# 03_-_MCU_and_Conn.net
KiCad netlist of a schematic drawn in Altium Designer
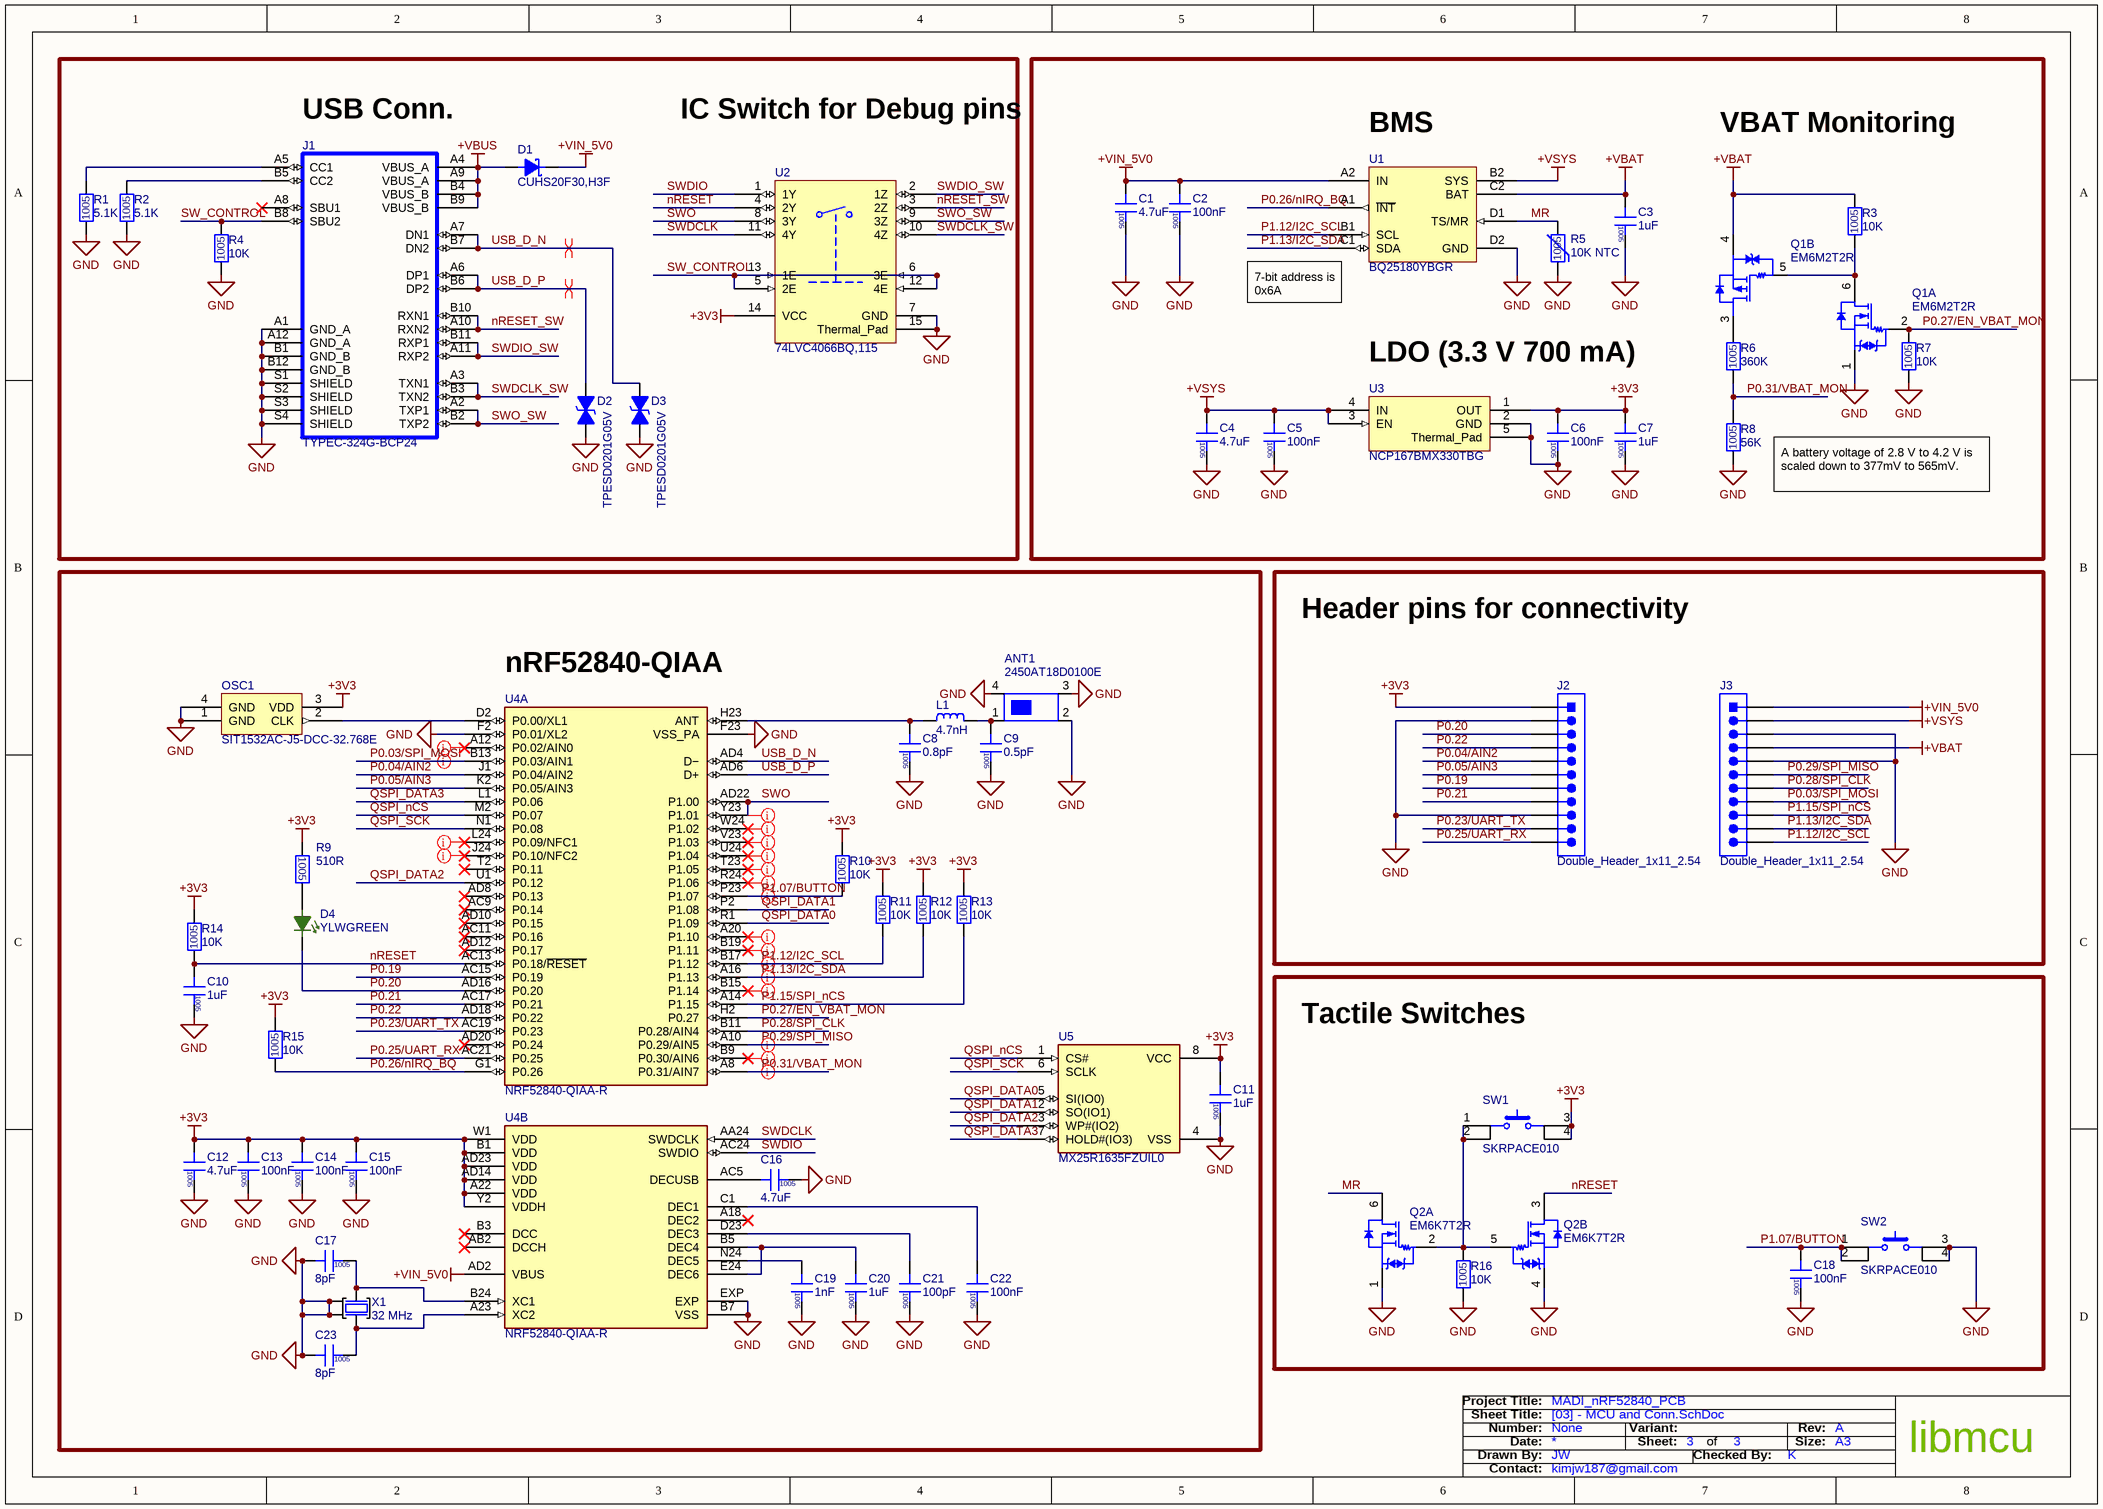
[diagram p0: [03] - MCU and Conn.SchDoc]

(export (version "E")
  (design (tool "Eeschema 10.0.6"))
  (components
    (comp (ref "ANT1")
      (value "2450AT18D0100E")
      (footprint "2450AT18D0100E")
      (description "RF ANT 2.4GHZ CHIP SOLDER SMD")
      (fields (field (name "MANUFACTURER") "Johanson"))
      (libsource (lib "Schlib-master") (part "2450AT18D0100E"))
    )
    (comp (ref "C1")
      (value "4.7uF")
      (footprint "CAPC1005X06N")
      (description "CAP CER 4.7UF 10V X5R 0402")
      (fields
        (field (name "MANUFACTURER") "Samsung")
        (field (name "MANUFACTURER PART NUMBER") "CL05A475MP5NRNC")
      )
      (libsource (lib "Schlib-master") (part "CL05A475MP5NRNC"))
    )
    (comp (ref "C2")
      (value "100nF")
      (footprint "CAPC1005X06N")
      (description "CAP CER 0.1UF 16V X7R 0402")
      (fields
        (field (name "MANUFACTURER") "Samsung")
        (field (name "MANUFACTURER PART NUMBER") "CL05B104KO5NNNC")
      )
      (libsource (lib "Schlib-master") (part "CL05B104KO5NNNC"))
    )
    (comp (ref "C3")
      (value "1uF")
      (footprint "CAPC1005X06N")
      (description "CAP CER 1UF 16V X5R 0402")
      (fields
        (field (name "MANUFACTURER") "Samsung")
        (field (name "MANUFACTURER PART NUMBER") "CL05A105KO5NNNC")
      )
      (libsource (lib "Schlib-master") (part "CL05A105KO5NNNC"))
    )
    (comp (ref "C4")
      (value "4.7uF")
      (footprint "CAPC1005X06N")
      (description "CAP CER 4.7UF 10V X5R 0402")
      (fields
        (field (name "MANUFACTURER") "Samsung")
        (field (name "MANUFACTURER PART NUMBER") "CL05A475MP5NRNC")
      )
      (libsource (lib "Schlib-master") (part "CL05A475MP5NRNC"))
    )
    (comp (ref "C5")
      (value "100nF")
      (footprint "CAPC1005X06N")
      (description "CAP CER 0.1UF 16V X7R 0402")
      (fields
        (field (name "MANUFACTURER") "Samsung")
        (field (name "MANUFACTURER PART NUMBER") "CL05B104KO5NNNC")
      )
      (libsource (lib "Schlib-master") (part "CL05B104KO5NNNC"))
    )
    (comp (ref "C6")
      (value "100nF")
      (footprint "CAPC1005X06N")
      (description "CAP CER 0.1UF 16V X7R 0402")
      (fields
        (field (name "MANUFACTURER") "Samsung")
        (field (name "MANUFACTURER PART NUMBER") "CL05B104KO5NNNC")
      )
      (libsource (lib "Schlib-master") (part "CL05B104KO5NNNC"))
    )
    (comp (ref "C7")
      (value "1uF")
      (footprint "CAPC1005X06N")
      (description "CAP CER 1UF 16V X5R 0402")
      (fields
        (field (name "MANUFACTURER") "Samsung")
        (field (name "MANUFACTURER PART NUMBER") "CL05A105KO5NNNC")
      )
      (libsource (lib "Schlib-master") (part "CL05A105KO5NNNC"))
    )
    (comp (ref "C8")
      (value "0.8pF")
      (footprint "CAPC1005X06N")
      (description "CAP CER 0.8PF 50V C0G/NP0 0402")
      (fields
        (field (name "MANUFACTURER") "Murata")
        (field (name "MANUFACTURER PART NUMBER") "GJM1555C1HR80BB01D")
      )
      (libsource (lib "Schlib-master") (part "GJM1555C1HR80BB01D"))
    )
    (comp (ref "C9")
      (value "0.5pF")
      (footprint "CAPC1005X06N")
      (description "CAP CER 0.5PF 50V C0G/NP0 0402")
      (fields
        (field (name "MANUFACTURER") "Murata")
        (field (name "MANUFACTURER PART NUMBER") "GJM1555C1HR50BB01D")
      )
      (libsource (lib "Schlib-master") (part "GJM1555C1HR50BB01D"))
    )
    (comp (ref "C10")
      (value "1uF")
      (footprint "CAPC1005X06N")
      (description "CAP CER 1UF 16V X5R 0402")
      (fields
        (field (name "MANUFACTURER") "Samsung")
        (field (name "MANUFACTURER PART NUMBER") "CL05A105KO5NNNC")
      )
      (libsource (lib "Schlib-master") (part "CL05A105KO5NNNC"))
    )
    (comp (ref "C11")
      (value "1uF")
      (footprint "CAPC1005X06N")
      (description "CAP CER 1UF 16V X5R 0402")
      (fields
        (field (name "MANUFACTURER") "Samsung")
        (field (name "MANUFACTURER PART NUMBER") "CL05A105KO5NNNC")
      )
      (libsource (lib "Schlib-master") (part "CL05A105KO5NNNC"))
    )
    (comp (ref "C12")
      (value "4.7uF")
      (footprint "CAPC1005X06N")
      (description "CAP CER 4.7UF 10V X5R 0402")
      (fields
        (field (name "MANUFACTURER") "Samsung")
        (field (name "MANUFACTURER PART NUMBER") "CL05A475MP5NRNC")
      )
      (libsource (lib "Schlib-master") (part "CL05A475MP5NRNC"))
    )
    (comp (ref "C13")
      (value "100nF")
      (footprint "CAPC1005X06N")
      (description "CAP CER 0.1UF 16V X7R 0402")
      (fields
        (field (name "MANUFACTURER") "Samsung")
        (field (name "MANUFACTURER PART NUMBER") "CL05B104KO5NNNC")
      )
      (libsource (lib "Schlib-master") (part "CL05B104KO5NNNC"))
    )
    (comp (ref "C14")
      (value "100nF")
      (footprint "CAPC1005X06N")
      (description "CAP CER 0.1UF 16V X7R 0402")
      (fields
        (field (name "MANUFACTURER") "Samsung")
        (field (name "MANUFACTURER PART NUMBER") "CL05B104KO5NNNC")
      )
      (libsource (lib "Schlib-master") (part "CL05B104KO5NNNC"))
    )
    (comp (ref "C15")
      (value "100nF")
      (footprint "CAPC1005X06N")
      (description "CAP CER 0.1UF 16V X7R 0402")
      (fields
        (field (name "MANUFACTURER") "Samsung")
        (field (name "MANUFACTURER PART NUMBER") "CL05B104KO5NNNC")
      )
      (libsource (lib "Schlib-master") (part "CL05B104KO5NNNC"))
    )
    (comp (ref "C16")
      (value "4.7uF")
      (footprint "CAPC1005X06N")
      (description "CAP CER 4.7UF 10V X5R 0402")
      (fields
        (field (name "MANUFACTURER") "Samsung")
        (field (name "MANUFACTURER PART NUMBER") "CL05A475MP5NRNC")
      )
      (libsource (lib "Schlib-master") (part "CL05A475MP5NRNC"))
    )
    (comp (ref "C17")
      (value "8pF")
      (footprint "CAPC1005X06N")
      (description "CAP CER 8PF 50V C0G/NP0 0402")
      (fields
        (field (name "MANUFACTURER") "Yageo")
        (field (name "MANUFACTURER PART NUMBER") "CC0402CRNPO9BN8R0")
      )
      (libsource (lib "Schlib-master") (part "CC0402CRNPO9BN8R0"))
    )
    (comp (ref "C18")
      (value "100nF")
      (footprint "CAPC1005X06N")
      (description "CAP CER 0.1UF 16V X7R 0402")
      (fields
        (field (name "MANUFACTURER") "Samsung")
        (field (name "MANUFACTURER PART NUMBER") "CL05B104KO5NNNC")
      )
      (libsource (lib "Schlib-master") (part "CL05B104KO5NNNC"))
    )
    (comp (ref "C19")
      (value "1nF")
      (footprint "CAPC1005X06N")
      (description "CAP CER 1000PF 50V X7R 0402")
      (fields
        (field (name "MANUFACTURER") "Samsung")
        (field (name "MANUFACTURER PART NUMBER") "CL05B102KB5NNNC")
      )
      (libsource (lib "Schlib-master") (part "CL05B102KB5NNNC"))
    )
    (comp (ref "C20")
      (value "1uF")
      (footprint "CAPC1005X06N")
      (description "CAP CER 1UF 16V X5R 0402")
      (fields
        (field (name "MANUFACTURER") "Samsung")
        (field (name "MANUFACTURER PART NUMBER") "CL05A105KO5NNNC")
      )
      (libsource (lib "Schlib-master") (part "CL05A105KO5NNNC"))
    )
    (comp (ref "C21")
      (value "100pF")
      (footprint "CAPC1005X06N")
      (description "CAP CER 100PF 50V C0G/NP0 0402")
      (fields
        (field (name "MANUFACTURER") "Samsung")
        (field (name "MANUFACTURER PART NUMBER") "CL05C101JB5NNNC")
      )
      (libsource (lib "Schlib-master") (part "CL05C101JB5NNNC"))
    )
    (comp (ref "C22")
      (value "100nF")
      (footprint "CAPC1005X06N")
      (description "CAP CER 0.1UF 16V X7R 0402")
      (fields
        (field (name "MANUFACTURER") "Samsung")
        (field (name "MANUFACTURER PART NUMBER") "CL05B104KO5NNNC")
      )
      (libsource (lib "Schlib-master") (part "CL05B104KO5NNNC"))
    )
    (comp (ref "C23")
      (value "8pF")
      (footprint "CAPC1005X06N")
      (description "CAP CER 8PF 50V C0G/NP0 0402")
      (fields
        (field (name "MANUFACTURER") "Yageo")
        (field (name "MANUFACTURER PART NUMBER") "CC0402CRNPO9BN8R0")
      )
      (libsource (lib "Schlib-master") (part "CC0402CRNPO9BN8R0"))
    )
    (comp (ref "D1")
      (value "CUHS20F30,H3F")
      (footprint "US2H-DIODE")
      (description "DIODE SCHOTTKY 30V 2A US2H")
      (fields (field (name "MANUFACTURER") "Toshiba"))
      (libsource (lib "Schlib-master") (part "CUHS20F30,H3F"))
    )
    (comp (ref "D2")
      (value "TPESD0201G05V")
      (footprint "DIOC0603X03N")
      (description "TVS DIODE 5.5VWM 40VC 0201")
      (fields (field (name "MANUFACTURER") "TECH PUBLIC"))
      (libsource (lib "Schlib-master") (part "TPESD0201G05V"))
    )
    (comp (ref "D3")
      (value "TPESD0201G05V")
      (footprint "DIOC0603X03N")
      (description "TVS DIODE 5.5VWM 40VC 0201")
      (fields (field (name "MANUFACTURER") "TECH PUBLIC"))
      (libsource (lib "Schlib-master") (part "TPESD0201G05V"))
    )
    (comp (ref "D4")
      (value "YLWGREEN")
      (footprint "LDIOC1608X08N")
      (description "LED YLW/GREEN DIFFUSED 1608 SMD")
      (fields
        (field (name "MANUFACTURER") "Everlight")
        (field (name "MANUFACTURER PART NUMBER") "19-217/G7C-AN1P2/3T")
      )
      (libsource (lib "Schlib-master") (part "19-217/G7C-AN1P2/3T"))
    )
    (comp (ref "J1")
      (value "TYPEC-324G-BCP24")
      (footprint "KUSBX-SMT3-CS-BTR_KYC")
      (description "CONN RCPT USB TYPE C, SMT PINS, TH SHIELD")
      (fields (field (name "MANUFACTURER") "XUNPU"))
      (libsource (lib "Schlib-master") (part "TYPEC-324G-BCP24"))
    )
    (comp (ref "J2")
      (value "Double_Header_1x11_2.54")
      (footprint "1x11_DOUBLE_HEADER_2.54")
      (libsource (lib "") (part "Double_Header_1x11_2.54_1"))
    )
    (comp (ref "J3")
      (value "Double_Header_1x11_2.54")
      (footprint "1x11_DOUBLE_HEADER_2.54")
      (libsource (lib "Schlib-master") (part "Double_Header_1x11_2.54"))
    )
    (comp (ref "L1")
      (value "4.7nH")
      (footprint "INDC1005X05N")
      (description "FIXED IND 4.7NH 400MA 180 MOHM")
      (fields
        (field (name "MANUFACTURER") "Chilisin Elec")
        (field (name "MANUFACTURER PART NUMBER") "CLH1005T-4N7S-S-NP")
      )
      (libsource (lib "Schlib-master") (part "CLH1005T-4N7S-S-NP"))
    )
    (comp (ref "OSC1")
      (value "SIT1532AC-J5-DCC-32.768E")
      (footprint "SIT1532")
      (description "MEMS OSC XO 32.7680KHZ LVCMOS")
      (fields (field (name "MANUFACTURER") "SiTime"))
      (libsource (lib "Schlib-master") (part "SIT1532AC-J5-DCC-32.768E"))
    )
    (comp (ref "Q1")
      (value "EM6M2T2R")
      (footprint "SOTFL50P160X55-6N")
      (description "MOSFET N/P-CH 20V 0.2A EMT6")
      (fields (field (name "MANUFACTURER") "Rohm"))
      (libsource (lib "Schlib-master") (part "EM6M2T2R"))
    )
    (comp (ref "Q2")
      (value "EM6K7T2R")
      (footprint "SOTFL50P160X55-6N")
      (description "MOSFET 2N-CH 20V 0.2A EMT6")
      (fields (field (name "MANUFACTURER") "Rohm"))
      (libsource (lib "Schlib-master") (part "EM6K7T2R"))
    )
    (comp (ref "R1")
      (value "5.1K")
      (footprint "RESC1005X04N")
      (description "RES SMD 5.1K OHM 1% 1/16W 0402")
      (fields
        (field (name "MANUFACTURER") "Yageo")
        (field (name "MANUFACTURER PART NUMBER") "RC0402FR-075K1L")
      )
      (libsource (lib "Schlib-master") (part "RC0402FR-075K1L"))
    )
    (comp (ref "R2")
      (value "5.1K")
      (footprint "RESC1005X04N")
      (description "RES SMD 5.1K OHM 1% 1/16W 0402")
      (fields
        (field (name "MANUFACTURER") "Yageo")
        (field (name "MANUFACTURER PART NUMBER") "RC0402FR-075K1L")
      )
      (libsource (lib "Schlib-master") (part "RC0402FR-075K1L"))
    )
    (comp (ref "R3")
      (value "10K")
      (footprint "RESC1005X04N")
      (description "RES SMD 10K OHM 1% 1/16W 0402")
      (fields
        (field (name "MANUFACTURER") "Yageo")
        (field (name "MANUFACTURER PART NUMBER") "RC0402FR-0710KL")
      )
      (libsource (lib "Schlib-master") (part "RC0402FR-0710KL"))
    )
    (comp (ref "R4")
      (value "10K")
      (footprint "RESC1005X04N")
      (description "RES SMD 10K OHM 1% 1/16W 0402")
      (fields
        (field (name "MANUFACTURER") "Yageo")
        (field (name "MANUFACTURER PART NUMBER") "RC0402FR-0710KL")
      )
      (libsource (lib "Schlib-master") (part "RC0402FR-0710KL"))
    )
    (comp (ref "R5")
      (value "10K NTC")
      (footprint "NTC1005X05N")
      (description "THERMISTOR NTC 10KOHM 3380K 0402")
      (fields
        (field (name "MANUFACTURER") "Murata")
        (field (name "MANUFACTURER PART NUMBER") "NCP15XH103F03RC")
      )
      (libsource (lib "Schlib-master") (part "NCP15XH103F03RC"))
    )
    (comp (ref "R6")
      (value "360K")
      (footprint "RESC1005X04N")
      (description "RES SMD 360K OHM 1% 1/16W 0402")
      (fields
        (field (name "MANUFACTURER") "Yageo")
        (field (name "MANUFACTURER PART NUMBER") "RC0402FR-07360KL")
      )
      (libsource (lib "Schlib-master") (part "RC0402FR-07360KL"))
    )
    (comp (ref "R7")
      (value "10K")
      (footprint "RESC1005X04N")
      (description "RES SMD 10K OHM 1% 1/16W 0402")
      (fields
        (field (name "MANUFACTURER") "Yageo")
        (field (name "MANUFACTURER PART NUMBER") "RC0402FR-0710KL")
      )
      (libsource (lib "Schlib-master") (part "RC0402FR-0710KL"))
    )
    (comp (ref "R8")
      (value "56K")
      (footprint "RESC1005X04N")
      (description "RES SMD 56K OHM 1% 1/16W 0402")
      (fields
        (field (name "MANUFACTURER") "Yageo")
        (field (name "MANUFACTURER PART NUMBER") "RC0402FR-0756KL")
      )
      (libsource (lib "Schlib-master") (part "RC0402FR-0756KL"))
    )
    (comp (ref "R9")
      (value "510R")
      (footprint "RESC1005X04N")
      (description "RES SMD 510 OHM 1% 1/16W 0402")
      (fields (field (name "TOLERANCE") "1%") (field (name "MANUFACTURER") "Yageo"))
      (libsource (lib "Schlib-master") (part "RC0402FR-07510RL"))
    )
    (comp (ref "R10")
      (value "10K")
      (footprint "RESC1005X04N")
      (description "RES SMD 10K OHM 1% 1/16W 0402")
      (fields
        (field (name "MANUFACTURER") "Yageo")
        (field (name "MANUFACTURER PART NUMBER") "RC0402FR-0710KL")
      )
      (libsource (lib "Schlib-master") (part "RC0402FR-0710KL"))
    )
    (comp (ref "R11")
      (value "10K")
      (footprint "RESC1005X04N")
      (description "RES SMD 10K OHM 1% 1/16W 0402")
      (fields
        (field (name "MANUFACTURER") "Yageo")
        (field (name "MANUFACTURER PART NUMBER") "RC0402FR-0710KL")
      )
      (libsource (lib "Schlib-master") (part "RC0402FR-0710KL"))
    )
    (comp (ref "R12")
      (value "10K")
      (footprint "RESC1005X04N")
      (description "RES SMD 10K OHM 1% 1/16W 0402")
      (fields
        (field (name "MANUFACTURER") "Yageo")
        (field (name "MANUFACTURER PART NUMBER") "RC0402FR-0710KL")
      )
      (libsource (lib "Schlib-master") (part "RC0402FR-0710KL"))
    )
    (comp (ref "R13")
      (value "10K")
      (footprint "RESC1005X04N")
      (description "RES SMD 10K OHM 1% 1/16W 0402")
      (fields
        (field (name "MANUFACTURER") "Yageo")
        (field (name "MANUFACTURER PART NUMBER") "RC0402FR-0710KL")
      )
      (libsource (lib "") (part "RC0402FR-0710KL_1"))
    )
    (comp (ref "R14")
      (value "10K")
      (footprint "RESC1005X04N")
      (description "RES SMD 10K OHM 1% 1/16W 0402")
      (fields
        (field (name "MANUFACTURER") "Yageo")
        (field (name "MANUFACTURER PART NUMBER") "RC0402FR-0710KL")
      )
      (libsource (lib "") (part "RC0402FR-0710KL_1"))
    )
    (comp (ref "R15")
      (value "10K")
      (footprint "RESC1005X04N")
      (description "RES SMD 10K OHM 1% 1/16W 0402")
      (fields
        (field (name "MANUFACTURER") "Yageo")
        (field (name "MANUFACTURER PART NUMBER") "RC0402FR-0710KL")
      )
      (libsource (lib "") (part "RC0402FR-0710KL_1"))
    )
    (comp (ref "R16")
      (value "10K")
      (footprint "RESC1005X04N")
      (description "RES SMD 10K OHM 1% 1/16W 0402")
      (fields
        (field (name "MANUFACTURER") "Yageo")
        (field (name "MANUFACTURER PART NUMBER") "RC0402FR-0710KL")
      )
      (libsource (lib "Schlib-master") (part "RC0402FR-0710KL"))
    )
    (comp (ref "SW1")
      (value "SKRPACE010")
      (footprint "PTS810")
      (description "SWITCH TACTILE SPST-NO 0.05A 16V")
      (fields (field (name "MANUFACTURER") "Alps Electric"))
      (libsource (lib "Schlib-master") (part "SKRPACE010"))
    )
    (comp (ref "SW2")
      (value "SKRPACE010")
      (footprint "PTS810")
      (description "SWITCH TACTILE SPST-NO 0.05A 16V")
      (fields (field (name "MANUFACTURER") "Alps Electric"))
      (libsource (lib "Schlib-master") (part "SKRPACE010"))
    )
    (comp (ref "U1")
      (value "BQ25180YBGR")
      (footprint "BGA8C40P2X4_100X155X50_YBG0008")
      (description "IC 1-A LI-ION IC PROGRAMMABLE CHARG")
      (fields (field (name "MANUFACTURER") "Texas Instruments"))
      (libsource (lib "Schlib-master") (part "BQ25180YBGR"))
    )
    (comp (ref "U2")
      (value "74LVC4066BQ,115")
      (footprint "QFN50P250X300X100_HS-15N")
      (description "IC SWITCH QUAD SPST 14DHVQFN")
      (fields (field (name "MANUFACTURER") "Nexperia"))
      (libsource (lib "Schlib-master") (part "74LVC4066BQ,115"))
    )
    (comp (ref "U3")
      (value "NCP167BMX330TBG")
      (footprint "NCP167")
      (description "IC REG LINEAR 3.3V 700MA 4XDFN")
      (fields (field (name "MANUFACTURER") "ON Semiconductor"))
      (libsource (lib "Schlib-master") (part "NCP167BMX330TBG"))
    )
    (comp (ref "U4")
      (value "NRF52840-QIAA-R")
      (footprint "NORDIC_NRF52840-QIAA-R7")
      (description "IC RF TXRX+MCU 802.15.4 73VFQFN")
      (fields (field (name "MANUFACTURER") "Nordic Semiconductor"))
      (libsource (lib "Schlib-master") (part "NRF52840-QIAA-R7"))
    )
    (comp (ref "U5")
      (value "MX25R1635FZUIL0")
      (footprint "USON8_3X2")
      (description "IC FLASH 16MBIT SPI/QUAD 8USON")
      (fields (field (name "MANUFACTURER") "Macronix"))
      (libsource (lib "Schlib-master") (part "MX25R1635FZUIL0"))
    )
    (comp (ref "X1")
      (value "32 MHz")
      (footprint "XT2016_ECS")
      (description "CRYSTAL 32.0000MHZ 8PF SMD")
      (fields
        (field (name "MANUFACTURER") "Seiko")
        (field (name "MANUFACTURER PART NUMBER") "Q22FA1280002500")
      )
      (libsource (lib "Schlib-master") (part "Q22FA1280002500"))
    )
  )
  (nets
    (net (code "1") (name "+3V3") (class "Default")
      (node (ref "C11") (pin "2") (pinfunction "2_2") (pintype "passive"))
      (node (ref "C12") (pin "2") (pinfunction "2_2") (pintype "passive"))
      (node (ref "C13") (pin "2") (pinfunction "2_2") (pintype "passive"))
      (node (ref "C14") (pin "2") (pinfunction "2_2") (pintype "passive"))
      (node (ref "C15") (pin "2") (pinfunction "2_2") (pintype "passive"))
      (node (ref "C6") (pin "2") (pinfunction "2_2") (pintype "passive"))
      (node (ref "C7") (pin "2") (pinfunction "2_2") (pintype "passive"))
      (node (ref "J2") (pin "1") (pinfunction "1_1") (pintype "passive"))
      (node (ref "OSC1") (pin "3") (pinfunction "VDD_3") (pintype "power_in"))
      (node (ref "R10") (pin "2") (pinfunction "2_2") (pintype "passive"))
      (node (ref "R11") (pin "2") (pinfunction "2_2") (pintype "passive"))
      (node (ref "R12") (pin "2") (pinfunction "2_2") (pintype "passive"))
      (node (ref "R13") (pin "2") (pinfunction "2_2") (pintype "passive"))
      (node (ref "R14") (pin "2") (pinfunction "2_2") (pintype "passive"))
      (node (ref "R15") (pin "2") (pinfunction "2_2") (pintype "passive"))
      (node (ref "R9") (pin "2") (pinfunction "2_2") (pintype "passive"))
      (node (ref "SW1") (pin "3") (pinfunction "2_3") (pintype "passive"))
      (node (ref "SW1") (pin "4") (pinfunction "1_4") (pintype "passive"))
      (node (ref "U2") (pin "14") (pinfunction "VCC_14") (pintype "power_in"))
      (node (ref "U3") (pin "1") (pinfunction "OUT_1") (pintype "power_in"))
      (node (ref "U4") (pin "A22") (pinfunction "VDD_A22") (pintype "power_in"))
      (node (ref "U4") (pin "AD14") (pinfunction "VDD_AD14") (pintype "power_in"))
      (node (ref "U4") (pin "AD23") (pinfunction "VDD_AD23") (pintype "power_in"))
      (node (ref "U4") (pin "B1") (pinfunction "VDD_B1") (pintype "power_in"))
      (node (ref "U4") (pin "W1") (pinfunction "VDD_W1") (pintype "power_in"))
      (node (ref "U4") (pin "Y2") (pinfunction "VDDH_Y2") (pintype "power_in"))
      (node (ref "U5") (pin "8") (pinfunction "VCC_8") (pintype "power_in"))
    )
    (net (code "2") (name "+VBAT") (class "Default")
      (node (ref "C3") (pin "2") (pinfunction "2_2") (pintype "passive"))
      (node (ref "J3") (pin "4") (pinfunction "4_4") (pintype "passive"))
      (node (ref "Q1") (pin "4") (pinfunction "S_4") (pintype "passive"))
      (node (ref "R3") (pin "2") (pinfunction "2_2") (pintype "passive"))
      (node (ref "U1") (pin "C2") (pinfunction "BAT_C2") (pintype "power_in"))
    )
    (net (code "3") (name "+VBUS") (class "Default")
      (node (ref "D1") (pin "2") (pinfunction "Anode_2") (pintype "passive"))
      (node (ref "J1") (pin "A4") (pinfunction "VBUS_A_A4") (pintype "power_in"))
      (node (ref "J1") (pin "A9") (pinfunction "VBUS_A_A9") (pintype "power_in"))
      (node (ref "J1") (pin "B4") (pinfunction "VBUS_B_B4") (pintype "power_in"))
      (node (ref "J1") (pin "B9") (pinfunction "VBUS_B_B9") (pintype "power_in"))
    )
    (net (code "4") (name "+VIN_5V0") (class "Default")
      (node (ref "C1") (pin "2") (pinfunction "2_2") (pintype "passive"))
      (node (ref "C2") (pin "2") (pinfunction "2_2") (pintype "passive"))
      (node (ref "D1") (pin "1") (pinfunction "Cathode_1") (pintype "passive"))
      (node (ref "J3") (pin "1") (pinfunction "1_1") (pintype "passive"))
      (node (ref "U1") (pin "A2") (pinfunction "IN_A2") (pintype "power_in"))
      (node (ref "U4") (pin "AD2") (pinfunction "VBUS_AD2") (pintype "power_in"))
    )
    (net (code "5") (name "+VSYS") (class "Default")
      (node (ref "C4") (pin "2") (pinfunction "2_2") (pintype "passive"))
      (node (ref "C5") (pin "2") (pinfunction "2_2") (pintype "passive"))
      (node (ref "J3") (pin "2") (pinfunction "2_2") (pintype "passive"))
      (node (ref "U1") (pin "B2") (pinfunction "SYS_B2") (pintype "power_in"))
      (node (ref "U3") (pin "3") (pinfunction "EN_3") (pintype "input"))
      (node (ref "U3") (pin "4") (pinfunction "IN_4") (pintype "power_in"))
    )
    (net (code "6") (name "/MR") (class "Default")
      (node (ref "Q2") (pin "6") (pinfunction "D_6") (pintype "passive"))
      (node (ref "R5") (pin "2") (pinfunction "2_2") (pintype "passive"))
      (node (ref "U1") (pin "D1") (pinfunction "TS/MR_D1") (pintype "input"))
    )
    (net (code "7") (name "/P0.03{slash}SPI_MOSI") (class "Default")
      (node (ref "J3") (pin "8") (pinfunction "8_8") (pintype "passive"))
      (node (ref "U4") (pin "B13") (pinfunction "P0.03/AIN1_B13") (pintype "bidirectional"))
    )
    (net (code "8") (name "/P0.04{slash}AIN2") (class "Default")
      (node (ref "J2") (pin "5") (pinfunction "5_5") (pintype "passive"))
      (node (ref "U4") (pin "J1") (pinfunction "P0.04/AIN2_J1") (pintype "bidirectional"))
    )
    (net (code "9") (name "/P0.05{slash}AIN3") (class "Default")
      (node (ref "J2") (pin "6") (pinfunction "6_6") (pintype "passive"))
      (node (ref "U4") (pin "K2") (pinfunction "P0.05/AIN3_K2") (pintype "bidirectional"))
    )
    (net (code "10") (name "/P0.19") (class "Default")
      (node (ref "J2") (pin "7") (pinfunction "7_7") (pintype "passive"))
      (node (ref "U4") (pin "AC15") (pinfunction "P0.19_AC15") (pintype "bidirectional"))
    )
    (net (code "11") (name "/P0.20") (class "Default")
      (node (ref "D4") (pin "K") (pinfunction "2_K") (pintype "passive"))
      (node (ref "J2") (pin "3") (pinfunction "3_3") (pintype "passive"))
      (node (ref "U4") (pin "AD16") (pinfunction "P0.20_AD16") (pintype "bidirectional"))
    )
    (net (code "12") (name "/P0.21") (class "Default")
      (node (ref "J2") (pin "8") (pinfunction "8_8") (pintype "passive"))
      (node (ref "U4") (pin "AC17") (pinfunction "P0.21_AC17") (pintype "bidirectional"))
    )
    (net (code "13") (name "/P0.22") (class "Default")
      (node (ref "J2") (pin "4") (pinfunction "4_4") (pintype "passive"))
      (node (ref "U4") (pin "AD18") (pinfunction "P0.22_AD18") (pintype "bidirectional"))
    )
    (net (code "14") (name "/P0.23{slash}UART_TX") (class "Default")
      (node (ref "J2") (pin "10") (pinfunction "10_10") (pintype "passive"))
      (node (ref "U4") (pin "AC19") (pinfunction "P0.23_AC19") (pintype "bidirectional"))
    )
    (net (code "15") (name "/P0.25{slash}UART_RX") (class "Default")
      (node (ref "J2") (pin "11") (pinfunction "11_11") (pintype "passive"))
      (node (ref "U4") (pin "AC21") (pinfunction "P0.25_AC21") (pintype "bidirectional"))
    )
    (net (code "16") (name "/P0.26{slash}nIRQ_BQ") (class "Default")
      (node (ref "R15") (pin "1") (pinfunction "1_1") (pintype "passive"))
      (node (ref "U1") (pin "A1") (pinfunction "~{INT}_A1") (pintype "output"))
      (node (ref "U4") (pin "G1") (pinfunction "P0.26_G1") (pintype "bidirectional"))
    )
    (net (code "17") (name "/P0.27{slash}EN_VBAT_MON") (class "Default")
      (node (ref "Q1") (pin "2") (pinfunction "G_2") (pintype "passive"))
      (node (ref "R7") (pin "2") (pinfunction "2_2") (pintype "passive"))
      (node (ref "U4") (pin "H2") (pinfunction "P0.27_H2") (pintype "bidirectional"))
    )
    (net (code "18") (name "/P0.28{slash}SPI_CLK") (class "Default")
      (node (ref "J3") (pin "7") (pinfunction "7_7") (pintype "passive"))
      (node (ref "U4") (pin "B11") (pinfunction "P0.28/AIN4_B11") (pintype "bidirectional"))
    )
    (net (code "19") (name "/P0.29{slash}SPI_MISO") (class "Default")
      (node (ref "J3") (pin "6") (pinfunction "6_6") (pintype "passive"))
      (node (ref "U4") (pin "A10") (pinfunction "P0.29/AIN5_A10") (pintype "bidirectional"))
    )
    (net (code "20") (name "/P0.31{slash}VBAT_MON") (class "Default")
      (node (ref "R6") (pin "1") (pinfunction "1_1") (pintype "passive"))
      (node (ref "R8") (pin "2") (pinfunction "2_2") (pintype "passive"))
      (node (ref "U4") (pin "A8") (pinfunction "P0.31/AIN7_A8") (pintype "bidirectional"))
    )
    (net (code "21") (name "/P1.07{slash}BUTTON") (class "Default")
      (node (ref "C18") (pin "2") (pinfunction "2_2") (pintype "passive"))
      (node (ref "R10") (pin "1") (pinfunction "1_1") (pintype "passive"))
      (node (ref "SW2") (pin "1") (pinfunction "1_1") (pintype "passive"))
      (node (ref "SW2") (pin "2") (pinfunction "2_2") (pintype "passive"))
      (node (ref "U4") (pin "P23") (pinfunction "P1.07_P23") (pintype "bidirectional"))
    )
    (net (code "22") (name "/P1.12{slash}I2C_SCL") (class "Default")
      (node (ref "J3") (pin "11") (pinfunction "11_11") (pintype "passive"))
      (node (ref "R11") (pin "1") (pinfunction "1_1") (pintype "passive"))
      (node (ref "U1") (pin "B1") (pinfunction "SCL_B1") (pintype "input"))
      (node (ref "U4") (pin "B17") (pinfunction "P1.12_B17") (pintype "bidirectional"))
    )
    (net (code "23") (name "/P1.13{slash}I2C_SDA") (class "Default")
      (node (ref "J3") (pin "10") (pinfunction "10_10") (pintype "passive"))
      (node (ref "R12") (pin "1") (pinfunction "1_1") (pintype "passive"))
      (node (ref "U1") (pin "C1") (pinfunction "SDA_C1") (pintype "bidirectional"))
      (node (ref "U4") (pin "A16") (pinfunction "P1.13_A16") (pintype "bidirectional"))
    )
    (net (code "24") (name "/P1.15{slash}SPI_nCS") (class "Default")
      (node (ref "J3") (pin "9") (pinfunction "9_9") (pintype "passive"))
      (node (ref "R13") (pin "1") (pinfunction "1_1") (pintype "passive"))
      (node (ref "U4") (pin "A14") (pinfunction "P1.15_A14") (pintype "bidirectional"))
    )
    (net (code "25") (name "/QSPI_DATA0") (class "Default")
      (node (ref "U4") (pin "R1") (pinfunction "P1.09_R1") (pintype "bidirectional"))
      (node (ref "U5") (pin "5") (pinfunction "SI(IO0)_5") (pintype "bidirectional"))
    )
    (net (code "26") (name "/QSPI_DATA1") (class "Default")
      (node (ref "U4") (pin "P2") (pinfunction "P1.08_P2") (pintype "bidirectional"))
      (node (ref "U5") (pin "2") (pinfunction "SO(IO1)_2") (pintype "bidirectional"))
    )
    (net (code "27") (name "/QSPI_DATA2") (class "Default")
      (node (ref "U4") (pin "U1") (pinfunction "P0.12_U1") (pintype "bidirectional"))
      (node (ref "U5") (pin "3") (pinfunction "WP#(IO2)_3") (pintype "bidirectional"))
    )
    (net (code "28") (name "/QSPI_DATA3") (class "Default")
      (node (ref "U4") (pin "L1") (pinfunction "P0.06_L1") (pintype "bidirectional"))
      (node (ref "U5") (pin "7") (pinfunction "HOLD#(IO3)_7") (pintype "bidirectional"))
    )
    (net (code "29") (name "/QSPI_SCK") (class "Default")
      (node (ref "U4") (pin "N1") (pinfunction "P0.08_N1") (pintype "bidirectional"))
      (node (ref "U5") (pin "6") (pinfunction "SCLK_6") (pintype "input"))
    )
    (net (code "30") (name "/QSPI_nCS") (class "Default")
      (node (ref "U4") (pin "M2") (pinfunction "P0.07_M2") (pintype "bidirectional"))
      (node (ref "U5") (pin "1") (pinfunction "CS#_1") (pintype "input"))
    )
    (net (code "31") (name "/SWDCLK") (class "Default")
      (node (ref "U2") (pin "11") (pinfunction "4Y_11") (pintype "bidirectional"))
      (node (ref "U4") (pin "AA24") (pinfunction "SWDCLK_AA24") (pintype "input"))
    )
    (net (code "32") (name "/SWDCLK_SW") (class "Default")
      (node (ref "J1") (pin "A3") (pinfunction "TXN1_A3") (pintype "bidirectional"))
      (node (ref "J1") (pin "B3") (pinfunction "TXN2_B3") (pintype "bidirectional"))
      (node (ref "U2") (pin "10") (pinfunction "4Z_10") (pintype "bidirectional"))
    )
    (net (code "33") (name "/SWDIO") (class "Default")
      (node (ref "U2") (pin "1") (pinfunction "1Y_1") (pintype "bidirectional"))
      (node (ref "U4") (pin "AC24") (pinfunction "SWDIO_AC24") (pintype "bidirectional"))
    )
    (net (code "34") (name "/SWDIO_SW") (class "Default")
      (node (ref "J1") (pin "A11") (pinfunction "RXP2_A11") (pintype "bidirectional"))
      (node (ref "J1") (pin "B11") (pinfunction "RXP1_B11") (pintype "bidirectional"))
      (node (ref "U2") (pin "2") (pinfunction "1Z_2") (pintype "bidirectional"))
    )
    (net (code "35") (name "/SWO") (class "Default")
      (node (ref "U2") (pin "8") (pinfunction "3Y_8") (pintype "bidirectional"))
      (node (ref "U4") (pin "AD22") (pinfunction "P1.00_AD22") (pintype "bidirectional"))
      (node (ref "U4") (pin "Y23") (pinfunction "P1.01_Y23") (pintype "bidirectional"))
    )
    (net (code "36") (name "/SWO_SW") (class "Default")
      (node (ref "J1") (pin "A2") (pinfunction "TXP1_A2") (pintype "bidirectional"))
      (node (ref "J1") (pin "B2") (pinfunction "TXP2_B2") (pintype "bidirectional"))
      (node (ref "U2") (pin "9") (pinfunction "3Z_9") (pintype "bidirectional"))
    )
    (net (code "37") (name "/SW_CONTROL") (class "Default")
      (node (ref "J1") (pin "B8") (pinfunction "SBU2_B8") (pintype "bidirectional"))
      (node (ref "R4") (pin "2") (pinfunction "2_2") (pintype "passive"))
      (node (ref "U2") (pin "12") (pinfunction "4E_12") (pintype "input"))
      (node (ref "U2") (pin "13") (pinfunction "1E_13") (pintype "input"))
      (node (ref "U2") (pin "5") (pinfunction "2E_5") (pintype "input"))
      (node (ref "U2") (pin "6") (pinfunction "3E_6") (pintype "input"))
    )
    (net (code "38") (name "/USB_D_N") (class "Default")
      (node (ref "D3") (pin "1") (pinfunction "1_1") (pintype "passive"))
      (node (ref "J1") (pin "A7") (pinfunction "DN1_A7") (pintype "bidirectional"))
      (node (ref "J1") (pin "B7") (pinfunction "DN2_B7") (pintype "bidirectional"))
      (node (ref "U4") (pin "AD4") (pinfunction "D−_AD4") (pintype "bidirectional"))
    )
    (net (code "39") (name "/USB_D_P") (class "Default")
      (node (ref "D2") (pin "1") (pinfunction "1_1") (pintype "passive"))
      (node (ref "J1") (pin "A6") (pinfunction "DP1_A6") (pintype "bidirectional"))
      (node (ref "J1") (pin "B6") (pinfunction "DP2_B6") (pintype "bidirectional"))
      (node (ref "U4") (pin "AD6") (pinfunction "D+_AD6") (pintype "bidirectional"))
    )
    (net (code "40") (name "/nRESET") (class "Default")
      (node (ref "C10") (pin "2") (pinfunction "2_2") (pintype "passive"))
      (node (ref "Q2") (pin "3") (pinfunction "D_3") (pintype "passive"))
      (node (ref "R14") (pin "1") (pinfunction "1_1") (pintype "passive"))
      (node (ref "U2") (pin "4") (pinfunction "2Y_4") (pintype "bidirectional"))
      (node (ref "U4") (pin "AC13") (pinfunction "P0.18/~{RESET}_AC13") (pintype "bidirectional"))
    )
    (net (code "41") (name "/nRESET_SW") (class "Default")
      (node (ref "J1") (pin "A10") (pinfunction "RXN2_A10") (pintype "bidirectional"))
      (node (ref "J1") (pin "B10") (pinfunction "RXN1_B10") (pintype "bidirectional"))
      (node (ref "U2") (pin "3") (pinfunction "2Z_3") (pintype "bidirectional"))
    )
    (net (code "42") (name "GND") (class "Default")
      (node (ref "ANT1") (pin "2") (pinfunction "GND_2") (pintype "passive"))
      (node (ref "ANT1") (pin "3") (pinfunction "GND_3") (pintype "passive"))
      (node (ref "ANT1") (pin "4") (pinfunction "GND_4") (pintype "passive"))
      (node (ref "C1") (pin "1") (pinfunction "1_1") (pintype "passive"))
      (node (ref "C10") (pin "1") (pinfunction "1_1") (pintype "passive"))
      (node (ref "C11") (pin "1") (pinfunction "1_1") (pintype "passive"))
      (node (ref "C12") (pin "1") (pinfunction "1_1") (pintype "passive"))
      (node (ref "C13") (pin "1") (pinfunction "1_1") (pintype "passive"))
      (node (ref "C14") (pin "1") (pinfunction "1_1") (pintype "passive"))
      (node (ref "C15") (pin "1") (pinfunction "1_1") (pintype "passive"))
      (node (ref "C16") (pin "1") (pinfunction "1_1") (pintype "passive"))
      (node (ref "C17") (pin "2") (pinfunction "2_2") (pintype "passive"))
      (node (ref "C18") (pin "1") (pinfunction "1_1") (pintype "passive"))
      (node (ref "C19") (pin "1") (pinfunction "1_1") (pintype "passive"))
      (node (ref "C2") (pin "1") (pinfunction "1_1") (pintype "passive"))
      (node (ref "C20") (pin "1") (pinfunction "1_1") (pintype "passive"))
      (node (ref "C21") (pin "1") (pinfunction "1_1") (pintype "passive"))
      (node (ref "C22") (pin "1") (pinfunction "1_1") (pintype "passive"))
      (node (ref "C23") (pin "2") (pinfunction "2_2") (pintype "passive"))
      (node (ref "C3") (pin "1") (pinfunction "1_1") (pintype "passive"))
      (node (ref "C4") (pin "1") (pinfunction "1_1") (pintype "passive"))
      (node (ref "C5") (pin "1") (pinfunction "1_1") (pintype "passive"))
      (node (ref "C6") (pin "1") (pinfunction "1_1") (pintype "passive"))
      (node (ref "C7") (pin "1") (pinfunction "1_1") (pintype "passive"))
      (node (ref "C8") (pin "1") (pinfunction "1_1") (pintype "passive"))
      (node (ref "C9") (pin "1") (pinfunction "1_1") (pintype "passive"))
      (node (ref "D2") (pin "2") (pinfunction "2_2") (pintype "passive"))
      (node (ref "D3") (pin "2") (pinfunction "2_2") (pintype "passive"))
      (node (ref "J1") (pin "A1") (pinfunction "GND_A_A1") (pintype "power_in"))
      (node (ref "J1") (pin "A12") (pinfunction "GND_A_A12") (pintype "power_in"))
      (node (ref "J1") (pin "B1") (pinfunction "GND_B_B1") (pintype "power_in"))
      (node (ref "J1") (pin "B12") (pinfunction "GND_B_B12") (pintype "power_in"))
      (node (ref "J1") (pin "S1") (pinfunction "SHIELD_S1") (pintype "passive"))
      (node (ref "J1") (pin "S2") (pinfunction "SHIELD_S2") (pintype "passive"))
      (node (ref "J1") (pin "S3") (pinfunction "SHIELD_S3") (pintype "passive"))
      (node (ref "J1") (pin "S4") (pinfunction "SHIELD_S4") (pintype "passive"))
      (node (ref "J2") (pin "2") (pinfunction "2_2") (pintype "passive"))
      (node (ref "J2") (pin "9") (pinfunction "9_9") (pintype "passive"))
      (node (ref "J3") (pin "3") (pinfunction "3_3") (pintype "passive"))
      (node (ref "J3") (pin "5") (pinfunction "5_5") (pintype "passive"))
      (node (ref "OSC1") (pin "1") (pinfunction "GND_1") (pintype "power_in"))
      (node (ref "OSC1") (pin "4") (pinfunction "GND_4") (pintype "power_in"))
      (node (ref "Q1") (pin "1") (pinfunction "S_1") (pintype "passive"))
      (node (ref "Q2") (pin "1") (pinfunction "S_1") (pintype "passive"))
      (node (ref "Q2") (pin "4") (pinfunction "S_4") (pintype "passive"))
      (node (ref "R1") (pin "1") (pinfunction "1_1") (pintype "passive"))
      (node (ref "R16") (pin "1") (pinfunction "1_1") (pintype "passive"))
      (node (ref "R2") (pin "1") (pinfunction "1_1") (pintype "passive"))
      (node (ref "R4") (pin "1") (pinfunction "1_1") (pintype "passive"))
      (node (ref "R5") (pin "1") (pinfunction "1_1") (pintype "passive"))
      (node (ref "R7") (pin "1") (pinfunction "1_1") (pintype "passive"))
      (node (ref "R8") (pin "1") (pinfunction "1_1") (pintype "passive"))
      (node (ref "SW2") (pin "3") (pinfunction "2_3") (pintype "passive"))
      (node (ref "SW2") (pin "4") (pinfunction "1_4") (pintype "passive"))
      (node (ref "U1") (pin "D2") (pinfunction "GND_D2") (pintype "power_in"))
      (node (ref "U2") (pin "15") (pinfunction "Thermal_Pad_15") (pintype "power_in"))
      (node (ref "U2") (pin "7") (pinfunction "GND_7") (pintype "power_in"))
      (node (ref "U3") (pin "2") (pinfunction "GND_2") (pintype "power_in"))
      (node (ref "U3") (pin "5") (pinfunction "Thermal_Pad_5") (pintype "passive"))
      (node (ref "U4") (pin "B7") (pinfunction "VSS_B7") (pintype "power_in"))
      (node (ref "U4") (pin "EXP") (pinfunction "EXP_EXP") (pintype "power_in"))
      (node (ref "U4") (pin "F2") (pinfunction "P0.01/XL2_F2") (pintype "bidirectional"))
      (node (ref "U4") (pin "F23") (pinfunction "VSS_PA_F23") (pintype "power_in"))
      (node (ref "U5") (pin "4") (pinfunction "VSS_4") (pintype "power_in"))
      (node (ref "X1") (pin "2") (pinfunction "GND_2") (pintype "passive"))
      (node (ref "X1") (pin "4") (pinfunction "GND_4") (pintype "passive"))
    )
    (net (code "43") (name "Net-(ANT1-FEED)") (class "Default")
      (node (ref "ANT1") (pin "1") (pinfunction "FEED_1") (pintype "passive"))
      (node (ref "C9") (pin "2") (pinfunction "2_2") (pintype "passive"))
      (node (ref "L1") (pin "2") (pinfunction "2_2") (pintype "passive"))
    )
    (net (code "44") (name "Net-(D4-1)") (class "Default")
      (node (ref "D4") (pin "A") (pinfunction "1_A") (pintype "passive"))
      (node (ref "R9") (pin "1") (pinfunction "1_1") (pintype "passive"))
    )
    (net (code "45") (name "Net-(J1-CC1)") (class "Default")
      (node (ref "J1") (pin "A5") (pinfunction "CC1_A5") (pintype "bidirectional"))
      (node (ref "R1") (pin "2") (pinfunction "2_2") (pintype "passive"))
    )
    (net (code "46") (name "Net-(J1-CC2)") (class "Default")
      (node (ref "J1") (pin "B5") (pinfunction "CC2_B5") (pintype "bidirectional"))
      (node (ref "R2") (pin "2") (pinfunction "2_2") (pintype "passive"))
    )
    (net (code "47") (name "Net-(OSC1-CLK)") (class "Default")
      (node (ref "OSC1") (pin "2") (pinfunction "CLK_2") (pintype "output"))
      (node (ref "U4") (pin "D2") (pinfunction "P0.00/XL1_D2") (pintype "bidirectional"))
    )
    (net (code "48") (name "Net-(Q1A-D)") (class "Default")
      (node (ref "Q1") (pin "5") (pinfunction "G_5") (pintype "passive"))
      (node (ref "Q1") (pin "6") (pinfunction "D_6") (pintype "passive"))
      (node (ref "R3") (pin "1") (pinfunction "1_1") (pintype "passive"))
    )
    (net (code "49") (name "Net-(Q1B-D)") (class "Default")
      (node (ref "Q1") (pin "3") (pinfunction "D_3") (pintype "passive"))
      (node (ref "R6") (pin "2") (pinfunction "2_2") (pintype "passive"))
    )
    (net (code "50") (name "Net-(Q2A-G)") (class "Default")
      (node (ref "Q2") (pin "2") (pinfunction "G_2") (pintype "passive"))
      (node (ref "Q2") (pin "5") (pinfunction "G_5") (pintype "passive"))
      (node (ref "R16") (pin "2") (pinfunction "2_2") (pintype "passive"))
      (node (ref "SW1") (pin "1") (pinfunction "1_1") (pintype "passive"))
      (node (ref "SW1") (pin "2") (pinfunction "2_2") (pintype "passive"))
    )
    (net (code "51") (name "Net-(U4A-ANT)") (class "Default")
      (node (ref "C8") (pin "2") (pinfunction "2_2") (pintype "passive"))
      (node (ref "L1") (pin "1") (pinfunction "1_1") (pintype "passive"))
      (node (ref "U4") (pin "H23") (pinfunction "ANT_H23") (pintype "bidirectional"))
    )
    (net (code "52") (name "Net-(U4B-DEC1)") (class "Default")
      (node (ref "C22") (pin "2") (pinfunction "2_2") (pintype "passive"))
      (node (ref "U4") (pin "C1") (pinfunction "DEC1_C1") (pintype "power_in"))
    )
    (net (code "53") (name "Net-(U4B-DEC3)") (class "Default")
      (node (ref "C21") (pin "2") (pinfunction "2_2") (pintype "passive"))
      (node (ref "U4") (pin "D23") (pinfunction "DEC3_D23") (pintype "power_in"))
    )
    (net (code "54") (name "Net-(U4B-DEC4)") (class "Default")
      (node (ref "C20") (pin "2") (pinfunction "2_2") (pintype "passive"))
      (node (ref "U4") (pin "B5") (pinfunction "DEC4_B5") (pintype "power_in"))
      (node (ref "U4") (pin "E24") (pinfunction "DEC6_E24") (pintype "power_in"))
    )
    (net (code "55") (name "Net-(U4B-DEC5)") (class "Default")
      (node (ref "C19") (pin "2") (pinfunction "2_2") (pintype "passive"))
      (node (ref "U4") (pin "N24") (pinfunction "DEC5_N24") (pintype "power_in"))
    )
    (net (code "56") (name "Net-(U4B-DECUSB)") (class "Default")
      (node (ref "C16") (pin "2") (pinfunction "2_2") (pintype "passive"))
      (node (ref "U4") (pin "AC5") (pinfunction "DECUSB_AC5") (pintype "power_in"))
    )
    (net (code "57") (name "Net-(U4B-XC1)") (class "Default")
      (node (ref "C17") (pin "1") (pinfunction "1_1") (pintype "passive"))
      (node (ref "U4") (pin "B24") (pinfunction "XC1_B24") (pintype "input"))
      (node (ref "X1") (pin "1") (pinfunction "IN_1") (pintype "passive"))
    )
    (net (code "58") (name "Net-(U4B-XC2)") (class "Default")
      (node (ref "C23") (pin "1") (pinfunction "1_1") (pintype "passive"))
      (node (ref "U4") (pin "A23") (pinfunction "XC2_A23") (pintype "input"))
      (node (ref "X1") (pin "3") (pinfunction "OUT_3") (pintype "passive"))
    )
    (net (code "59") (name "unconnected-(J1-SBU1-PadA8)") (class "Default")
      (node (ref "J1") (pin "A8") (pinfunction "SBU1_A8") (pintype "bidirectional+no_connect"))
    )
    (net (code "60") (name "unconnected-(U4A-P0.02{slash}AIN0-PadA12)") (class "Default")
      (node (ref "U4") (pin "A12") (pinfunction "P0.02/AIN0_A12") (pintype "bidirectional+no_connect"))
    )
    (net (code "61") (name "unconnected-(U4A-P0.09{slash}NFC1-PadL24)") (class "Default")
      (node (ref "U4") (pin "L24") (pinfunction "P0.09/NFC1_L24") (pintype "bidirectional+no_connect"))
    )
    (net (code "62") (name "unconnected-(U4A-P0.10{slash}NFC2-PadJ24)") (class "Default")
      (node (ref "U4") (pin "J24") (pinfunction "P0.10/NFC2_J24") (pintype "bidirectional+no_connect"))
    )
    (net (code "63") (name "unconnected-(U4A-P0.11-PadT2)") (class "Default")
      (node (ref "U4") (pin "T2") (pinfunction "P0.11_T2") (pintype "bidirectional+no_connect"))
    )
    (net (code "64") (name "unconnected-(U4A-P0.13-PadAD8)") (class "Default")
      (node (ref "U4") (pin "AD8") (pinfunction "P0.13_AD8") (pintype "bidirectional+no_connect"))
    )
    (net (code "65") (name "unconnected-(U4A-P0.14-PadAC9)") (class "Default")
      (node (ref "U4") (pin "AC9") (pinfunction "P0.14_AC9") (pintype "bidirectional+no_connect"))
    )
    (net (code "66") (name "unconnected-(U4A-P0.15-PadAD10)") (class "Default")
      (node (ref "U4") (pin "AD10") (pinfunction "P0.15_AD10") (pintype "bidirectional+no_connect"))
    )
    (net (code "67") (name "unconnected-(U4A-P0.16-PadAC11)") (class "Default")
      (node (ref "U4") (pin "AC11") (pinfunction "P0.16_AC11") (pintype "bidirectional+no_connect"))
    )
    (net (code "68") (name "unconnected-(U4A-P0.17-PadAD12)") (class "Default")
      (node (ref "U4") (pin "AD12") (pinfunction "P0.17_AD12") (pintype "bidirectional+no_connect"))
    )
    (net (code "69") (name "unconnected-(U4A-P0.24-PadAD20)") (class "Default")
      (node (ref "U4") (pin "AD20") (pinfunction "P0.24_AD20") (pintype "bidirectional+no_connect"))
    )
    (net (code "70") (name "unconnected-(U4A-P0.30{slash}AIN6-PadB9)") (class "Default")
      (node (ref "U4") (pin "B9") (pinfunction "P0.30/AIN6_B9") (pintype "bidirectional+no_connect"))
    )
    (net (code "71") (name "unconnected-(U4A-P1.02-PadW24)") (class "Default")
      (node (ref "U4") (pin "W24") (pinfunction "P1.02_W24") (pintype "bidirectional+no_connect"))
    )
    (net (code "72") (name "unconnected-(U4A-P1.03-PadV23)") (class "Default")
      (node (ref "U4") (pin "V23") (pinfunction "P1.03_V23") (pintype "bidirectional+no_connect"))
    )
    (net (code "73") (name "unconnected-(U4A-P1.04-PadU24)") (class "Default")
      (node (ref "U4") (pin "U24") (pinfunction "P1.04_U24") (pintype "bidirectional+no_connect"))
    )
    (net (code "74") (name "unconnected-(U4A-P1.05-PadT23)") (class "Default")
      (node (ref "U4") (pin "T23") (pinfunction "P1.05_T23") (pintype "bidirectional+no_connect"))
    )
    (net (code "75") (name "unconnected-(U4A-P1.06-PadR24)") (class "Default")
      (node (ref "U4") (pin "R24") (pinfunction "P1.06_R24") (pintype "bidirectional+no_connect"))
    )
    (net (code "76") (name "unconnected-(U4A-P1.10-PadA20)") (class "Default")
      (node (ref "U4") (pin "A20") (pinfunction "P1.10_A20") (pintype "bidirectional+no_connect"))
    )
    (net (code "77") (name "unconnected-(U4A-P1.11-PadB19)") (class "Default")
      (node (ref "U4") (pin "B19") (pinfunction "P1.11_B19") (pintype "bidirectional+no_connect"))
    )
    (net (code "78") (name "unconnected-(U4A-P1.14-PadB15)") (class "Default")
      (node (ref "U4") (pin "B15") (pinfunction "P1.14_B15") (pintype "bidirectional+no_connect"))
    )
    (net (code "79") (name "unconnected-(U4B-DCC-PadB3)") (class "Default")
      (node (ref "U4") (pin "B3") (pinfunction "DCC_B3") (pintype "power_in+no_connect"))
    )
    (net (code "80") (name "unconnected-(U4B-DCCH-PadAB2)") (class "Default")
      (node (ref "U4") (pin "AB2") (pinfunction "DCCH_AB2") (pintype "power_in+no_connect"))
    )
    (net (code "81") (name "unconnected-(U4B-DEC2-PadA18)") (class "Default")
      (node (ref "U4") (pin "A18") (pinfunction "DEC2_A18") (pintype "power_in+no_connect"))
    )
  )
)
